# JTAG_Trace.net
KiCad netlist of a schematic drawn in Altium Designer
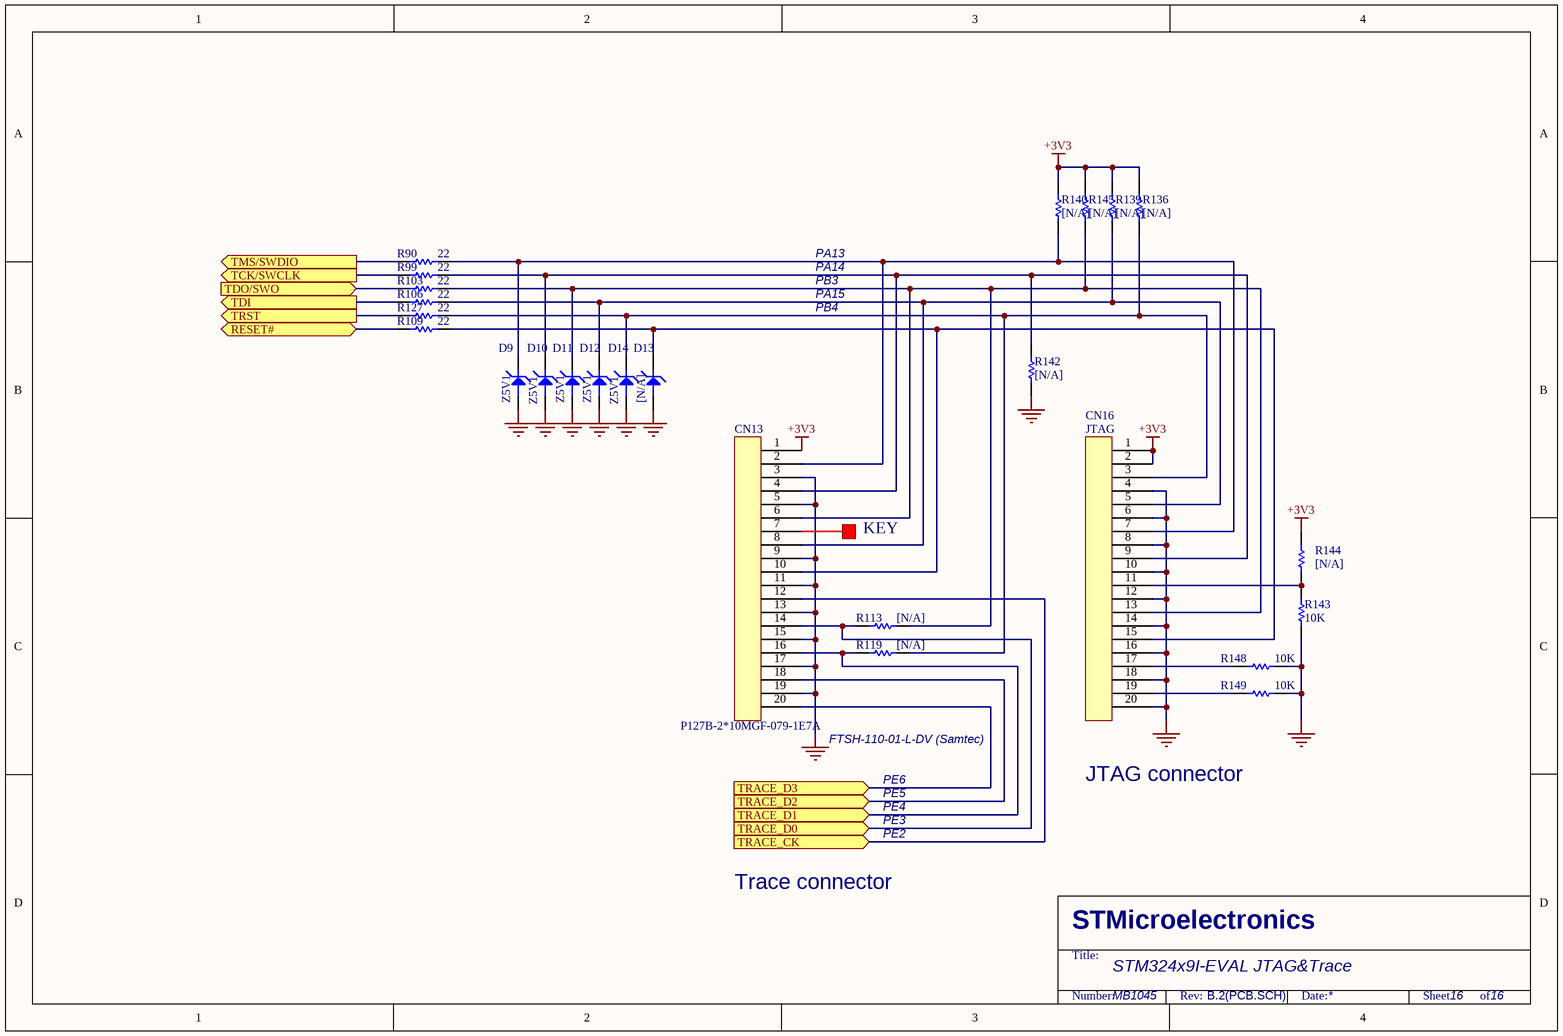
[diagram p0: JTAG&Trace.SchDoc]

(export (version "E")
  (design (tool "Eeschema 10.0.6"))
  (components
    (comp (ref "CN13")
      (value "P127B-2*10MGF-079-1E7A")
      (footprint "FTSH-110-01-L-DV")
      (libsource (lib "*") (part "20PIN1"))
    )
    (comp (ref "CN16") (value "JTAG") (footprint "IDC20S") (libsource (lib "*") (part "20PIN1")))
    (comp (ref "D9") (value "Z5V1") (footprint "SOT23-213") (libsource (lib "mb1045") (part "BATS5V6")))
    (comp (ref "D10") (value "Z5V1") (footprint "SOT23-213") (libsource (lib "mb1045") (part "BATS5V6")))
    (comp (ref "D11") (value "Z5V1") (footprint "SOT23-213") (libsource (lib "mb1045") (part "BATS5V6")))
    (comp (ref "D12") (value "Z5V1") (footprint "SOT23-213") (libsource (lib "mb1045") (part "BATS5V6")))
    (comp (ref "D13") (value "[N/A]") (footprint "SOT23-213") (libsource (lib "mb1045") (part "BATS5V6")))
    (comp (ref "D14") (value "Z5V1") (footprint "SOT23-213") (libsource (lib "mb1045") (part "BATS5V6")))
    (comp (ref "R90")
      (value "22")
      (footprint "0603R")
      (description "Resistor")
      (fields (field (name "PUBLISHER") "Altium Limited"))
      (libsource (lib "Miscellaneous Devices") (part "Res1"))
    )
    (comp (ref "R99")
      (value "22")
      (footprint "0603R")
      (description "Resistor")
      (fields (field (name "PUBLISHER") "Altium Limited"))
      (libsource (lib "Miscellaneous Devices") (part "Res1"))
    )
    (comp (ref "R103")
      (value "22")
      (footprint "0603R")
      (description "Resistor")
      (fields (field (name "PUBLISHER") "Altium Limited"))
      (libsource (lib "Miscellaneous Devices") (part "Res1"))
    )
    (comp (ref "R106")
      (value "22")
      (footprint "0603R")
      (description "Resistor")
      (fields (field (name "PUBLISHER") "Altium Limited"))
      (libsource (lib "Miscellaneous Devices") (part "Res1"))
    )
    (comp (ref "R109")
      (value "22")
      (footprint "0603R")
      (description "Resistor")
      (fields (field (name "PUBLISHER") "Altium Limited"))
      (libsource (lib "Miscellaneous Devices") (part "Res1"))
    )
    (comp (ref "R113")
      (value "[N/A]")
      (footprint "0603R")
      (description "Resistor")
      (fields (field (name "PUBLISHER") "Altium Limited"))
      (libsource (lib "Miscellaneous Devices") (part "Res1"))
    )
    (comp (ref "R119")
      (value "[N/A]")
      (footprint "0603R")
      (description "Resistor")
      (fields (field (name "PUBLISHER") "Altium Limited"))
      (libsource (lib "Miscellaneous Devices") (part "Res1"))
    )
    (comp (ref "R127")
      (value "22")
      (footprint "0603R")
      (description "Resistor")
      (fields (field (name "PUBLISHER") "Altium Limited"))
      (libsource (lib "Miscellaneous Devices") (part "Res1"))
    )
    (comp (ref "R136")
      (value "[N/A]")
      (footprint "0603R")
      (description "Resistor")
      (fields (field (name "PUBLISHER") "Altium Limited"))
      (libsource (lib "Miscellaneous Devices") (part "Res1"))
    )
    (comp (ref "R139")
      (value "[N/A]")
      (footprint "0603R")
      (description "Resistor")
      (fields (field (name "PUBLISHER") "Altium Limited"))
      (libsource (lib "Miscellaneous Devices") (part "Res1"))
    )
    (comp (ref "R140")
      (value "[N/A]")
      (footprint "0603R")
      (description "Resistor")
      (fields (field (name "PUBLISHER") "Altium Limited"))
      (libsource (lib "Miscellaneous Devices") (part "Res1"))
    )
    (comp (ref "R142")
      (value "[N/A]")
      (footprint "0603R")
      (description "Resistor")
      (fields (field (name "PUBLISHER") "Altium Limited"))
      (libsource (lib "Miscellaneous Devices") (part "Res1"))
    )
    (comp (ref "R143")
      (value "10K")
      (footprint "0603R")
      (description "Resistor")
      (fields (field (name "PUBLISHER") "Altium Limited"))
      (libsource (lib "Miscellaneous Devices") (part "Res1"))
    )
    (comp (ref "R144")
      (value "[N/A]")
      (footprint "0603R")
      (description "Resistor")
      (fields (field (name "PUBLISHER") "Altium Limited"))
      (libsource (lib "Miscellaneous Devices") (part "Res1"))
    )
    (comp (ref "R145")
      (value "[N/A]")
      (footprint "0603R")
      (description "Resistor")
      (fields (field (name "PUBLISHER") "Altium Limited"))
      (libsource (lib "Miscellaneous Devices") (part "Res1"))
    )
    (comp (ref "R148")
      (value "10K")
      (footprint "0603R")
      (description "Resistor")
      (fields (field (name "PUBLISHER") "Altium Limited"))
      (libsource (lib "Miscellaneous Devices") (part "Res1"))
    )
    (comp (ref "R149")
      (value "10K")
      (footprint "0603R")
      (description "Resistor")
      (fields (field (name "PUBLISHER") "Altium Limited"))
      (libsource (lib "Miscellaneous Devices") (part "Res1"))
    )
  )
  (nets
    (net (code "1") (name "+3V3") (class "Default")
      (node (ref "CN13") (pin "1") (pintype "passive"))
      (node (ref "CN16") (pin "1") (pintype "passive"))
      (node (ref "CN16") (pin "2") (pintype "passive"))
      (node (ref "R136") (pin "2") (pinfunction "2_2") (pintype "passive"))
      (node (ref "R139") (pin "2") (pinfunction "2_2") (pintype "passive"))
      (node (ref "R140") (pin "2") (pinfunction "2_2") (pintype "passive"))
      (node (ref "R144") (pin "2") (pinfunction "2_2") (pintype "passive"))
      (node (ref "R145") (pin "2") (pinfunction "2_2") (pintype "passive"))
    )
    (net (code "2") (name "/RESET#") (class "Default")
      (node (ref "R109") (pin "2") (pinfunction "2_2") (pintype "passive"))
    )
    (net (code "3") (name "/TCK{slash}SWCLK") (class "Default")
      (node (ref "R99") (pin "2") (pinfunction "2_2") (pintype "passive"))
    )
    (net (code "4") (name "/TDI") (class "Default")
      (node (ref "R106") (pin "2") (pinfunction "2_2") (pintype "passive"))
    )
    (net (code "5") (name "/TDO{slash}SWO") (class "Default")
      (node (ref "R103") (pin "2") (pinfunction "2_2") (pintype "passive"))
    )
    (net (code "6") (name "/TMS{slash}SWDIO") (class "Default")
      (node (ref "R90") (pin "2") (pinfunction "2_2") (pintype "passive"))
    )
    (net (code "7") (name "/TRACE_CK") (class "Default") (node (ref "CN13") (pin "12") (pintype "passive")))
    (net (code "8") (name "/TRACE_D0") (class "Default")
      (node (ref "CN13") (pin "14") (pintype "passive"))
      (node (ref "R113") (pin "1") (pinfunction "1_1") (pintype "passive"))
    )
    (net (code "9") (name "/TRACE_D1") (class "Default")
      (node (ref "CN13") (pin "16") (pintype "passive"))
      (node (ref "R119") (pin "1") (pinfunction "1_1") (pintype "passive"))
    )
    (net (code "10") (name "/TRACE_D2") (class "Default") (node (ref "CN13") (pin "18") (pintype "passive")))
    (net (code "11") (name "/TRACE_D3") (class "Default") (node (ref "CN13") (pin "20") (pintype "passive")))
    (net (code "12") (name "/TRST") (class "Default")
      (node (ref "R127") (pin "2") (pinfunction "2_2") (pintype "passive"))
    )
    (net (code "13") (name "GND") (class "Default")
      (node (ref "CN13") (pin "11") (pintype "passive"))
      (node (ref "CN13") (pin "13") (pintype "passive"))
      (node (ref "CN13") (pin "15") (pintype "passive"))
      (node (ref "CN13") (pin "17") (pintype "passive"))
      (node (ref "CN13") (pin "19") (pintype "passive"))
      (node (ref "CN13") (pin "3") (pintype "passive"))
      (node (ref "CN13") (pin "5") (pintype "passive"))
      (node (ref "CN13") (pin "9") (pintype "passive"))
      (node (ref "CN16") (pin "10") (pintype "passive"))
      (node (ref "CN16") (pin "12") (pintype "passive"))
      (node (ref "CN16") (pin "14") (pintype "passive"))
      (node (ref "CN16") (pin "16") (pintype "passive"))
      (node (ref "CN16") (pin "18") (pintype "passive"))
      (node (ref "CN16") (pin "20") (pintype "passive"))
      (node (ref "CN16") (pin "4") (pintype "passive"))
      (node (ref "CN16") (pin "6") (pintype "passive"))
      (node (ref "CN16") (pin "8") (pintype "passive"))
      (node (ref "D10") (pin "2") (pintype "passive"))
      (node (ref "D11") (pin "2") (pintype "passive"))
      (node (ref "D12") (pin "2") (pintype "passive"))
      (node (ref "D13") (pin "2") (pintype "passive"))
      (node (ref "D14") (pin "2") (pintype "passive"))
      (node (ref "D9") (pin "2") (pintype "passive"))
      (node (ref "R142") (pin "1") (pinfunction "1_1") (pintype "passive"))
      (node (ref "R143") (pin "1") (pinfunction "1_1") (pintype "passive"))
      (node (ref "R148") (pin "1") (pinfunction "1_1") (pintype "passive"))
      (node (ref "R149") (pin "1") (pinfunction "1_1") (pintype "passive"))
    )
    (net (code "14") (name "Net-(CN13-Pad2)") (class "Default")
      (node (ref "CN13") (pin "2") (pintype "passive"))
      (node (ref "CN16") (pin "7") (pintype "passive"))
      (node (ref "D9") (pin "3") (pintype "passive"))
      (node (ref "R140") (pin "1") (pinfunction "1_1") (pintype "passive"))
      (node (ref "R90") (pin "1") (pinfunction "1_1") (pintype "passive"))
    )
    (net (code "15") (name "Net-(CN13-Pad4)") (class "Default")
      (node (ref "CN13") (pin "4") (pintype "passive"))
      (node (ref "CN16") (pin "9") (pintype "passive"))
      (node (ref "D10") (pin "3") (pintype "passive"))
      (node (ref "R142") (pin "2") (pinfunction "2_2") (pintype "passive"))
      (node (ref "R99") (pin "1") (pinfunction "1_1") (pintype "passive"))
    )
    (net (code "16") (name "Net-(CN13-Pad6)") (class "Default")
      (node (ref "CN13") (pin "6") (pintype "passive"))
      (node (ref "CN16") (pin "13") (pintype "passive"))
      (node (ref "D11") (pin "3") (pintype "passive"))
      (node (ref "R103") (pin "1") (pinfunction "1_1") (pintype "passive"))
      (node (ref "R113") (pin "2") (pinfunction "2_2") (pintype "passive"))
      (node (ref "R145") (pin "1") (pinfunction "1_1") (pintype "passive"))
    )
    (net (code "17") (name "Net-(CN13-Pad8)") (class "Default")
      (node (ref "CN13") (pin "8") (pintype "passive"))
      (node (ref "CN16") (pin "5") (pintype "passive"))
      (node (ref "D12") (pin "3") (pintype "passive"))
      (node (ref "R106") (pin "1") (pinfunction "1_1") (pintype "passive"))
      (node (ref "R139") (pin "1") (pinfunction "1_1") (pintype "passive"))
    )
    (net (code "18") (name "Net-(CN13-Pad10)") (class "Default")
      (node (ref "CN13") (pin "10") (pintype "passive"))
      (node (ref "CN16") (pin "15") (pintype "passive"))
      (node (ref "D13") (pin "3") (pintype "passive"))
      (node (ref "R109") (pin "1") (pinfunction "1_1") (pintype "passive"))
    )
    (net (code "19") (name "Net-(CN16-Pad3)") (class "Default")
      (node (ref "CN16") (pin "3") (pintype "passive"))
      (node (ref "D14") (pin "3") (pintype "passive"))
      (node (ref "R119") (pin "2") (pinfunction "2_2") (pintype "passive"))
      (node (ref "R127") (pin "1") (pinfunction "1_1") (pintype "passive"))
      (node (ref "R136") (pin "1") (pinfunction "1_1") (pintype "passive"))
    )
    (net (code "20") (name "Net-(CN16-Pad11)") (class "Default")
      (node (ref "CN16") (pin "11") (pintype "passive"))
      (node (ref "R143") (pin "2") (pinfunction "2_2") (pintype "passive"))
      (node (ref "R144") (pin "1") (pinfunction "1_1") (pintype "passive"))
    )
    (net (code "21") (name "Net-(CN16-Pad17)") (class "Default")
      (node (ref "CN16") (pin "17") (pintype "passive"))
      (node (ref "R148") (pin "2") (pinfunction "2_2") (pintype "passive"))
    )
    (net (code "22") (name "Net-(CN16-Pad19)") (class "Default")
      (node (ref "CN16") (pin "19") (pintype "passive"))
      (node (ref "R149") (pin "2") (pinfunction "2_2") (pintype "passive"))
    )
    (net (code "23") (name "unconnected-(CN13-Pad7)") (class "Default")
      (node (ref "CN13") (pin "7") (pintype "passive"))
    )
  )
)
